# LKS_074DO_0406.net
KiCad netlist of a schematic drawn in Altium Designer
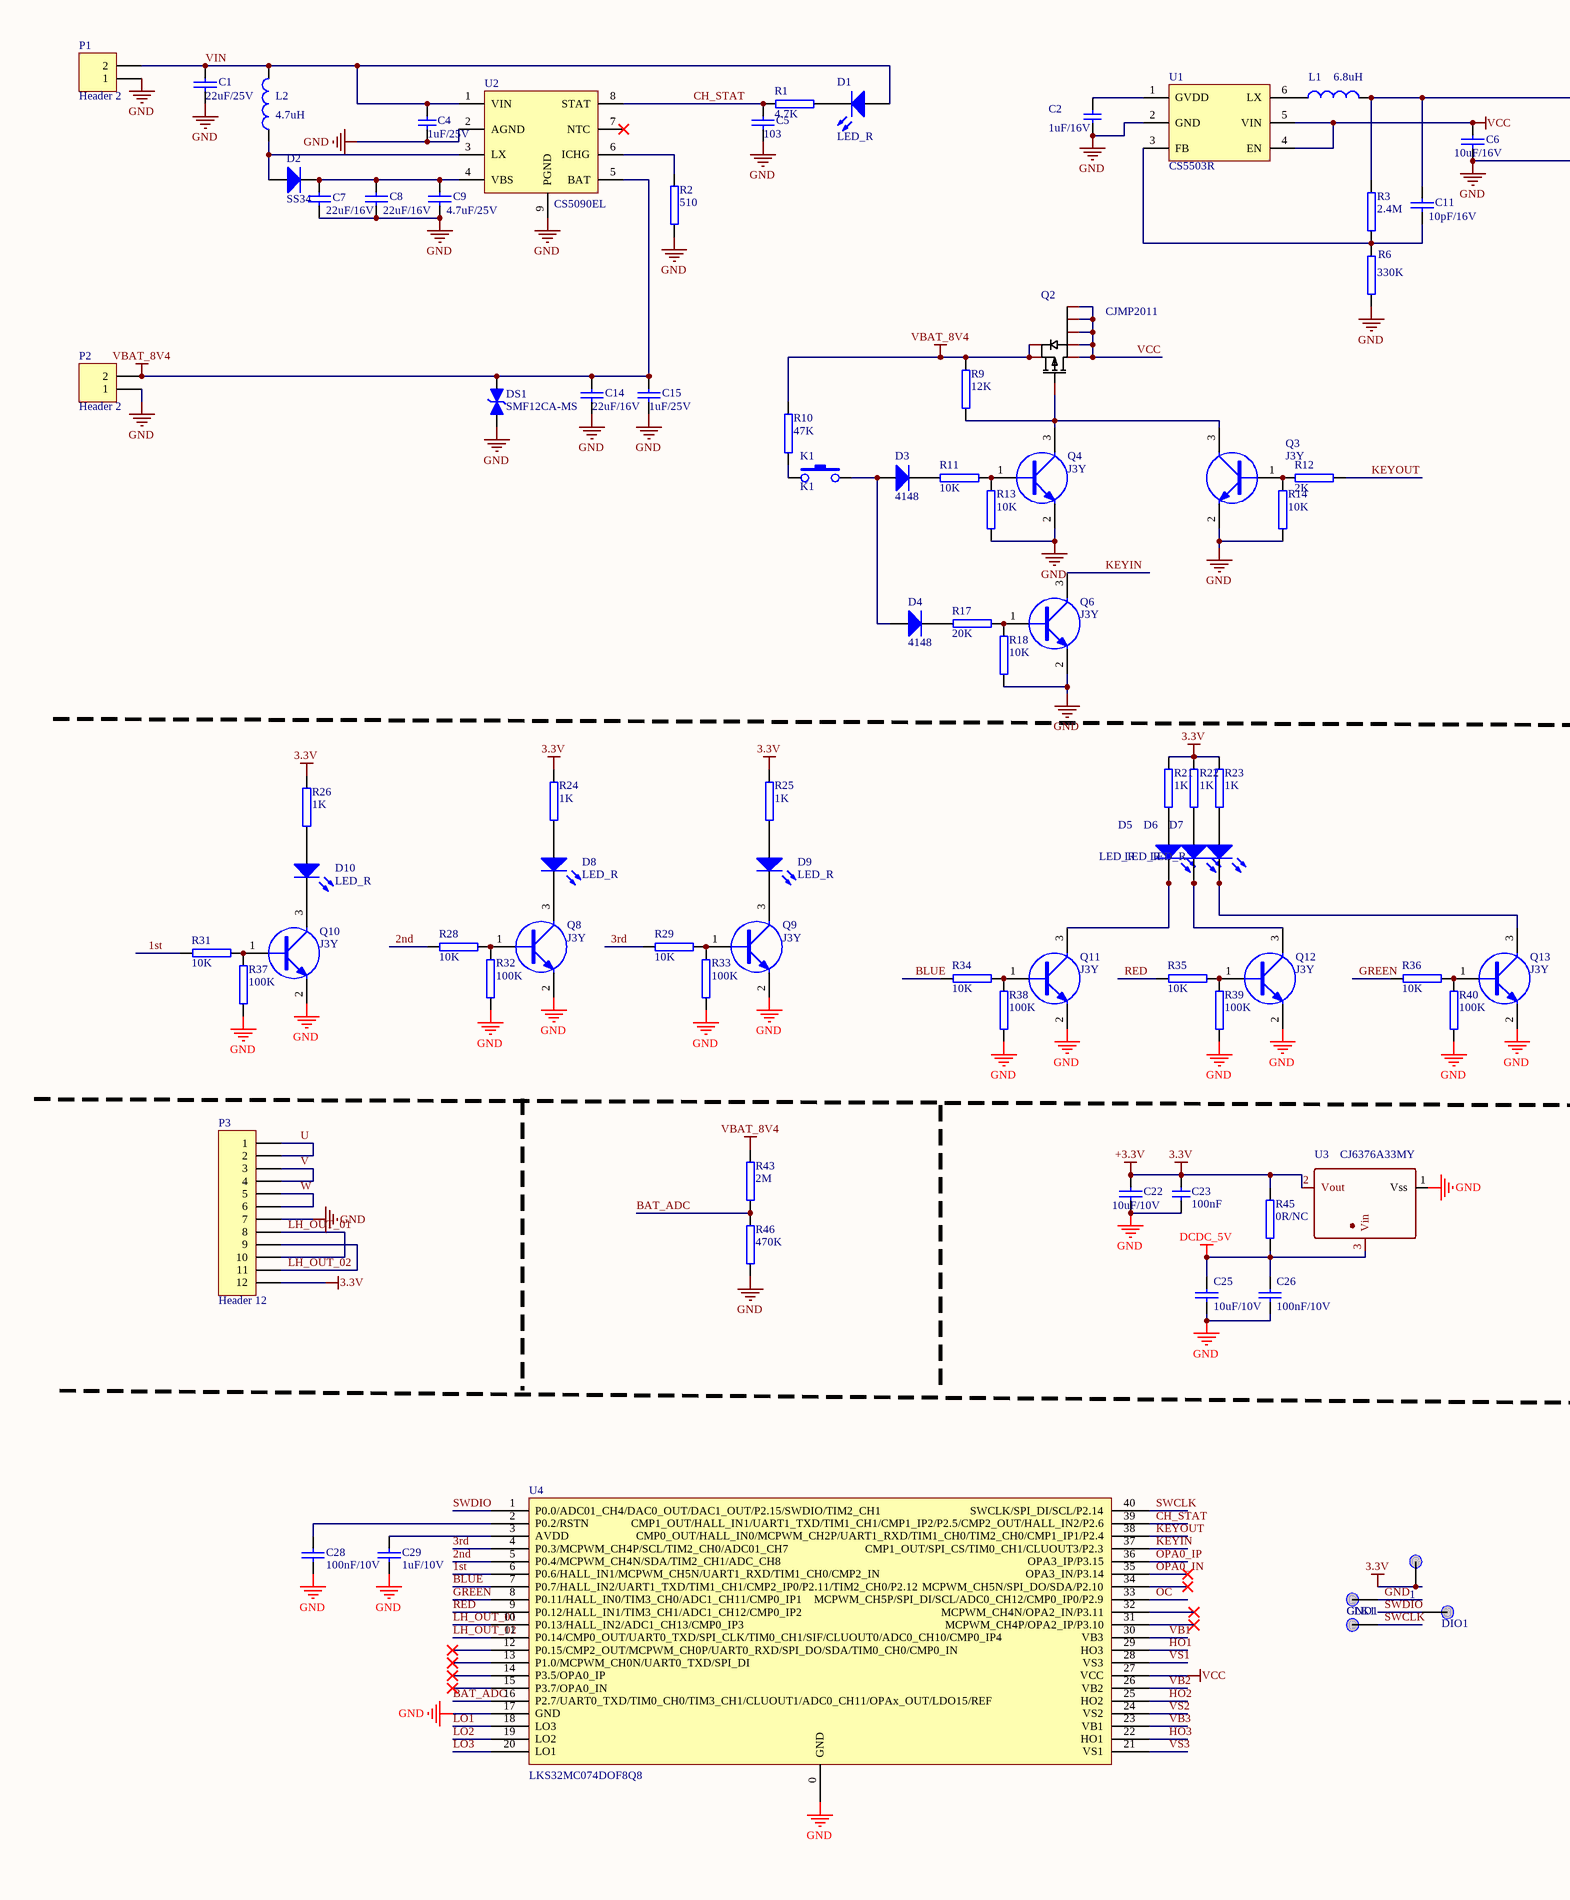
[diagram p0: LKS_074DO_0406.SchDoc, left]
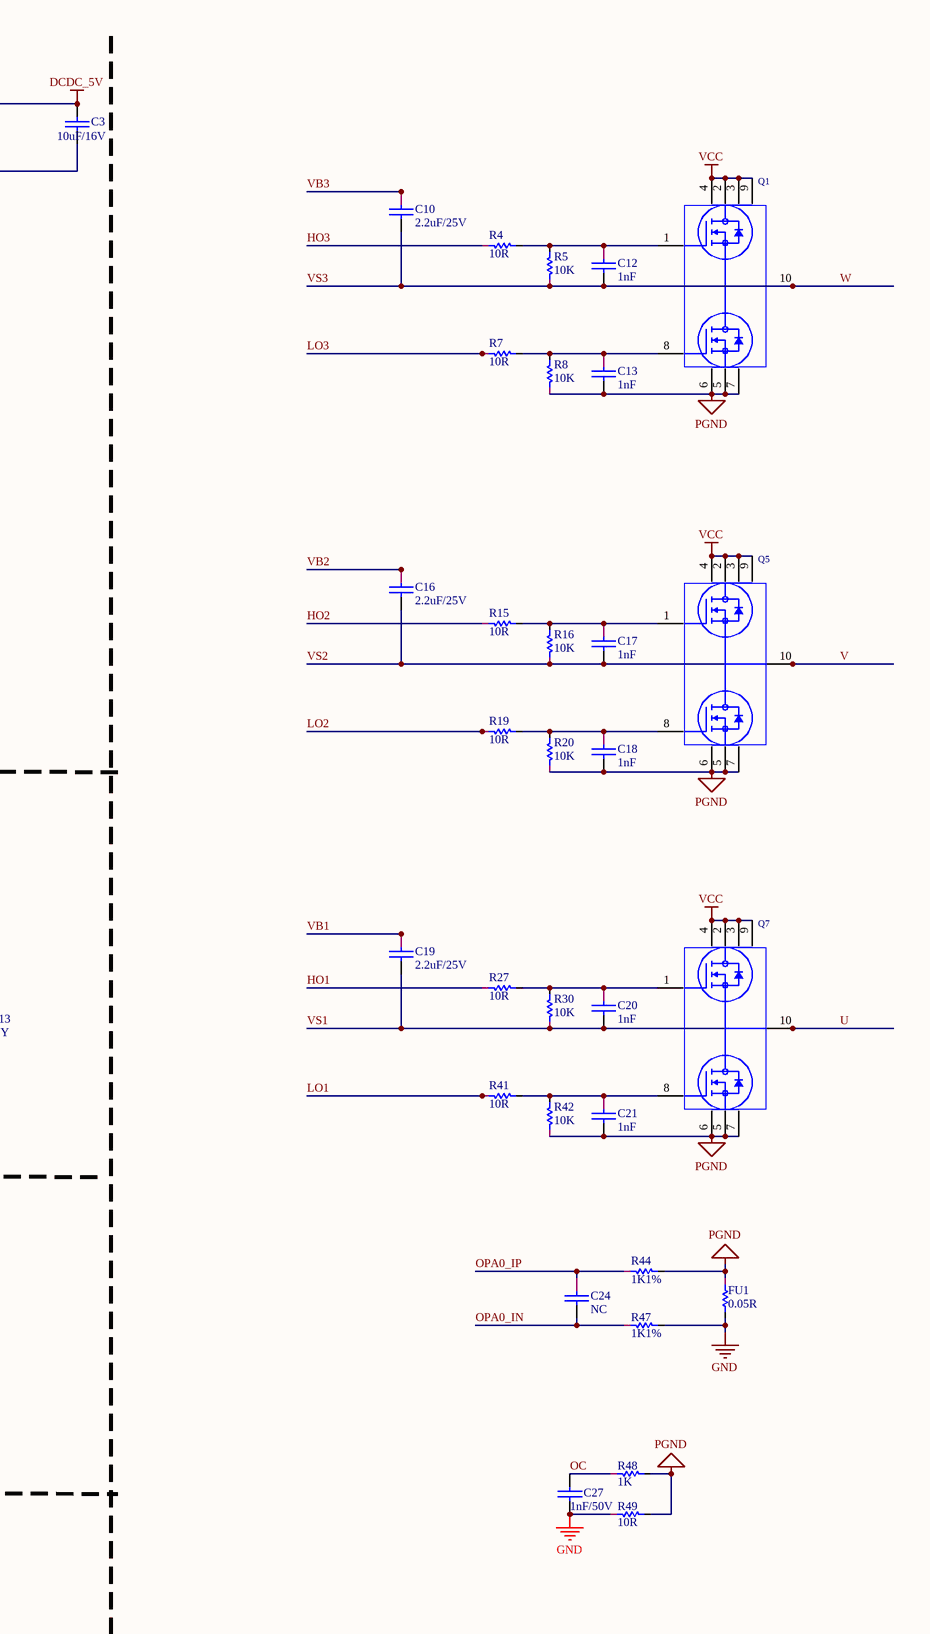
[diagram p1: LKS_074DO_0406.SchDoc, right]

(export (version "E")
  (design (tool "Eeschema 10.0.6"))
  (components
    (comp (ref "1") (value "test") (footprint "piot") (libsource (lib "LKS074DO_BRUSH_0329") (part "test")))
    (comp (ref "C1")
      (value "22uF/25V")
      (footprint "C 0603_M")
      (description "Capacitor")
      (libsource (lib "") (part "CAP_1"))
    )
    (comp (ref "C2") (value "1uF/16V") (footprint "C 0402_M") (libsource (lib "") (part "CAP_2")))
    (comp (ref "C3")
      (value "10uF/16V")
      (footprint "C 0603_M")
      (description "Capacitor")
      (libsource (lib "") (part "CAP_1"))
    )
    (comp (ref "C4") (value "1uF/25V") (footprint "C 0402_M") (libsource (lib "") (part "CAP_2")))
    (comp (ref "C5")
      (value "103")
      (footprint "R 0402_M")
      (description "Capacitor")
      (libsource (lib "") (part "CAP_1"))
    )
    (comp (ref "C6")
      (value "10uF/16V")
      (footprint "C 0603_M")
      (description "Capacitor")
      (libsource (lib "") (part "CAP_1"))
    )
    (comp (ref "C7")
      (value "22uF/16V")
      (footprint "C 0603_M")
      (description "Capacitor")
      (libsource (lib "") (part "CAP_1"))
    )
    (comp (ref "C8")
      (value "22uF/16V")
      (footprint "C 0603_M")
      (description "Capacitor")
      (libsource (lib "") (part "CAP_1"))
    )
    (comp (ref "C9")
      (value "4.7uF/25V")
      (footprint "C 0402_M")
      (description "Capacitor")
      (libsource (lib "") (part "CAP_1"))
    )
    (comp (ref "C10")
      (value "2.2uF/25V")
      (footprint "C 0402_M")
      (description "Capacitor")
      (libsource (lib "*") (part "CAP"))
    )
    (comp (ref "C11")
      (value "10pF/16V")
      (footprint "C 0402_M")
      (description "Capacitor")
      (libsource (lib "") (part "CAP_1"))
    )
    (comp (ref "C12")
      (value "1nF")
      (footprint "C 0402_M")
      (description "Capacitor")
      (libsource (lib "*") (part "CAP"))
    )
    (comp (ref "C13")
      (value "1nF")
      (footprint "C 0402_M")
      (description "Capacitor")
      (libsource (lib "*") (part "CAP"))
    )
    (comp (ref "C14")
      (value "22uF/16V")
      (footprint "C 0603_M")
      (description "Capacitor")
      (libsource (lib "") (part "CAP_1"))
    )
    (comp (ref "C15")
      (value "1uF/25V")
      (footprint "C 0402_M")
      (description "Capacitor")
      (libsource (lib "") (part "CAP_1"))
    )
    (comp (ref "C16")
      (value "2.2uF/25V")
      (footprint "C 0402_M")
      (description "Capacitor")
      (libsource (lib "*") (part "CAP"))
    )
    (comp (ref "C17")
      (value "1nF")
      (footprint "C 0402_M")
      (description "Capacitor")
      (libsource (lib "*") (part "CAP"))
    )
    (comp (ref "C18")
      (value "1nF")
      (footprint "C 0402_M")
      (description "Capacitor")
      (libsource (lib "*") (part "CAP"))
    )
    (comp (ref "C19")
      (value "2.2uF/25V")
      (footprint "C 0402_M")
      (description "Capacitor")
      (libsource (lib "*") (part "CAP"))
    )
    (comp (ref "C20")
      (value "1nF")
      (footprint "C 0402_M")
      (description "Capacitor")
      (libsource (lib "*") (part "CAP"))
    )
    (comp (ref "C21")
      (value "1nF")
      (footprint "C 0402_M")
      (description "Capacitor")
      (libsource (lib "*") (part "CAP"))
    )
    (comp (ref "C22")
      (value "10uF/10V")
      (footprint "C 0603_M")
      (description "Capacitor")
      (libsource (lib "") (part "CAP_1"))
    )
    (comp (ref "C23") (value "100nF") (footprint "C 0402_M") (libsource (lib "") (part "CAP_2")))
    (comp (ref "C24")
      (value "NC")
      (footprint "C 0402_M")
      (description "Capacitor")
      (libsource (lib "*") (part "CAP"))
    )
    (comp (ref "C25")
      (value "10uF/10V")
      (footprint "C 0603_M")
      (description "Capacitor")
      (libsource (lib "") (part "CAP_1"))
    )
    (comp (ref "C26")
      (value "100nF/10V")
      (footprint "C 0402_M")
      (description "Capacitor")
      (libsource (lib "") (part "CAP_1"))
    )
    (comp (ref "C27")
      (value "1nF/50V")
      (footprint "C 0402_M")
      (description "Capacitor")
      (libsource (lib "*") (part "C"))
    )
    (comp (ref "C28")
      (value "100nF/10V")
      (footprint "C 0402_M")
      (description "Capacitor")
      (libsource (lib "*") (part "C"))
    )
    (comp (ref "C29")
      (value "1uF/10V")
      (footprint "C 0402_M")
      (description "Capacitor")
      (libsource (lib "*") (part "C"))
    )
    (comp (ref "CLK1")
      (value "test")
      (footprint "piot")
      (libsource (lib "LKS074DO_BRUSH_0329") (part "test"))
    )
    (comp (ref "D1") (value "LED_R") (footprint "0603-LED") (libsource (lib "PuXun1") (part "LED")))
    (comp (ref "D2")
      (value "SS34")
      (footprint "SOD123FL")
      (description "Default Diode")
      (fields (field (name "PUBLISHER") "Altium Limited"))
      (libsource (lib "LKS034DO_Motor_0520_1") (part "Diode"))
    )
    (comp (ref "D3")
      (value "4148")
      (footprint "SOD-323")
      (description "Default Diode")
      (fields (field (name "PUBLISHER") "Altium Limited"))
      (libsource (lib "LKS034DO_Motor_0520_1") (part "Diode"))
    )
    (comp (ref "D4")
      (value "4148")
      (footprint "SOD-323")
      (description "Default Diode")
      (fields (field (name "PUBLISHER") "Altium Limited"))
      (libsource (lib "LKS034DO_Motor_0520_1") (part "Diode"))
    )
    (comp (ref "D5") (value "LED_R") (footprint "0603-LED") (libsource (lib "PuXun1") (part "LED")))
    (comp (ref "D6") (value "LED_R") (footprint "0603-LED") (libsource (lib "PuXun1") (part "LED")))
    (comp (ref "D7") (value "LED_R") (footprint "0603-LED") (libsource (lib "PuXun1") (part "LED")))
    (comp (ref "D8") (value "LED_R") (footprint "0603-LED") (libsource (lib "PuXun1") (part "LED")))
    (comp (ref "D9") (value "LED_R") (footprint "0603-LED") (libsource (lib "PuXun1") (part "LED")))
    (comp (ref "D10") (value "LED_R") (footprint "0603-LED") (libsource (lib "PuXun1") (part "LED")))
    (comp (ref "DIO1")
      (value "test")
      (footprint "piot")
      (libsource (lib "LKS074DO_BRUSH_0329") (part "test"))
    )
    (comp (ref "DS1")
      (value "SMF12CA-MS")
      (footprint "SOD-123F")
      (description "12V/19.9V")
      (libsource (lib "*") (part "DIODE-3"))
    )
    (comp (ref "FU1") (value "0.05R") (footprint "R 0805_M") (libsource (lib "*") (part "RAS")))
    (comp (ref "GND1")
      (value "test")
      (footprint "piot")
      (libsource (lib "LKS074DO_BRUSH_0329") (part "test"))
    )
    (comp (ref "K1") (value "K1") (footprint "SMD3.3X3.3X2") (libsource (lib "SCHLIB_NEW") (part "K1")))
    (comp (ref "L1")
      (value "6.8uH")
      (footprint "SMD3.5X3 .2- duplicate")
      (description "Inductor")
      (fields (field (name "PUBLISHER") "Altium Limited"))
      (libsource (lib "Miscellaneous Devices") (part "Inductor"))
    )
    (comp (ref "L2")
      (value "4.7uH")
      (footprint "SMD3.5X3 .2- duplicate")
      (description "Inductor")
      (fields (field (name "PUBLISHER") "Altium Limited"))
      (libsource (lib "Miscellaneous Devices") (part "Inductor"))
    )
    (comp (ref "P1")
      (value "Header 2")
      (footprint "CONN_SMD_2P_0.6")
      (description "Header, 2-Pin")
      (fields (field (name "PUBLISHER") "Altium Limited"))
      (libsource (lib "Miscellaneous Connectors") (part "Header 2"))
    )
    (comp (ref "P2")
      (value "Header 2")
      (footprint "CONN_SMD_2P_0.6")
      (description "Header, 2-Pin")
      (fields (field (name "PUBLISHER") "Altium Limited"))
      (libsource (lib "Miscellaneous Connectors") (part "Header 2"))
    )
    (comp (ref "P3")
      (value "Header 12")
      (footprint "SMD-12")
      (description "Header, 12-Pin")
      (fields (field (name "PUBLISHER") "Altium Limited"))
      (libsource (lib "Miscellaneous Connectors") (part "Header 12"))
    )
    (comp (ref "Q1") (value "CJBM3020") (footprint "DFN-3X3_8") (libsource (lib "*") (part "CJBM3020")))
    (comp (ref "Q2")
      (value "CJMP2011")
      (footprint "DFN-6-2X2")
      (libsource (lib "LKS074DO_BRUSH_0329") (part "CJMP2011"))
    )
    (comp (ref "Q3")
      (value "J3Y")
      (footprint "SOT-23")
      (description "NPN Transistor")
      (libsource (lib "*") (part "NPN"))
    )
    (comp (ref "Q4")
      (value "J3Y")
      (footprint "SOT-23")
      (description "NPN Transistor")
      (libsource (lib "*") (part "NPN"))
    )
    (comp (ref "Q5") (value "CJBM3020") (footprint "DFN-3X3_8") (libsource (lib "*") (part "CJBM3020")))
    (comp (ref "Q6")
      (value "J3Y")
      (footprint "SOT-23")
      (description "NPN Transistor")
      (libsource (lib "*") (part "NPN"))
    )
    (comp (ref "Q7") (value "CJBM3020") (footprint "DFN-3X3_8") (libsource (lib "*") (part "CJBM3020")))
    (comp (ref "Q8")
      (value "J3Y")
      (footprint "SOT-23")
      (description "NPN Transistor")
      (libsource (lib "*") (part "NPN"))
    )
    (comp (ref "Q9")
      (value "J3Y")
      (footprint "SOT-23")
      (description "NPN Transistor")
      (libsource (lib "*") (part "NPN"))
    )
    (comp (ref "Q10")
      (value "J3Y")
      (footprint "SOT-23")
      (description "NPN Transistor")
      (libsource (lib "*") (part "NPN"))
    )
    (comp (ref "Q11")
      (value "J3Y")
      (footprint "SOT-23")
      (description "NPN Transistor")
      (libsource (lib "*") (part "NPN"))
    )
    (comp (ref "Q12")
      (value "J3Y")
      (footprint "SOT-23")
      (description "NPN Transistor")
      (libsource (lib "*") (part "NPN"))
    )
    (comp (ref "Q13")
      (value "J3Y")
      (footprint "SOT-23")
      (description "NPN Transistor")
      (libsource (lib "*") (part "NPN"))
    )
    (comp (ref "R1") (value "4.7K") (footprint "C 0402_M") (libsource (lib "*") (part "RES2_S")))
    (comp (ref "R2") (value "510") (footprint "R 0402_M") (libsource (lib "*") (part "RES2_S")))
    (comp (ref "R3") (value "2.4M") (footprint "C 0402_M") (libsource (lib "*") (part "RES2_S")))
    (comp (ref "R4") (value "10R") (footprint "R 0402_M") (libsource (lib "*") (part "RAS")))
    (comp (ref "R5") (value "10K") (footprint "R 0402_M") (libsource (lib "*") (part "RAS")))
    (comp (ref "R6") (value "330K") (footprint "C 0402_M") (libsource (lib "*") (part "RES2_S")))
    (comp (ref "R7") (value "10R") (footprint "R 0402_M") (libsource (lib "*") (part "RAS")))
    (comp (ref "R8") (value "10K") (footprint "R 0402_M") (libsource (lib "*") (part "RAS")))
    (comp (ref "R9") (value "12K") (footprint "C 0402_M") (libsource (lib "*") (part "RES2_S")))
    (comp (ref "R10") (value "47K") (footprint "C 0402_M") (libsource (lib "*") (part "RES2_S")))
    (comp (ref "R11") (value "10K") (footprint "C 0402_M") (libsource (lib "*") (part "RES2_S")))
    (comp (ref "R12") (value "2K") (footprint "C 0402_M") (libsource (lib "*") (part "RES2_S")))
    (comp (ref "R13") (value "10K") (footprint "C 0402_M") (libsource (lib "*") (part "RES2_S")))
    (comp (ref "R14") (value "10K") (footprint "C 0402_M") (libsource (lib "*") (part "RES2_S")))
    (comp (ref "R15") (value "10R") (footprint "R 0402_M") (libsource (lib "*") (part "RAS")))
    (comp (ref "R16") (value "10K") (footprint "R 0402_M") (libsource (lib "*") (part "RAS")))
    (comp (ref "R17") (value "20K") (footprint "C 0402_M") (libsource (lib "*") (part "RES2_S")))
    (comp (ref "R18") (value "10K") (footprint "C 0402_M") (libsource (lib "*") (part "RES2_S")))
    (comp (ref "R19") (value "10R") (footprint "R 0402_M") (libsource (lib "*") (part "RAS")))
    (comp (ref "R20") (value "10K") (footprint "R 0402_M") (libsource (lib "*") (part "RAS")))
    (comp (ref "R21") (value "1K") (footprint "C 0402_M") (libsource (lib "*") (part "RES2_S")))
    (comp (ref "R22") (value "1K") (footprint "C 0402_M") (libsource (lib "*") (part "RES2_S")))
    (comp (ref "R23") (value "1K") (footprint "C 0402_M") (libsource (lib "*") (part "RES2_S")))
    (comp (ref "R24") (value "1K") (footprint "C 0402_M") (libsource (lib "*") (part "RES2_S")))
    (comp (ref "R25") (value "1K") (footprint "C 0402_M") (libsource (lib "*") (part "RES2_S")))
    (comp (ref "R26") (value "1K") (footprint "C 0402_M") (libsource (lib "*") (part "RES2_S")))
    (comp (ref "R27") (value "10R") (footprint "R 0402_M") (libsource (lib "*") (part "RAS")))
    (comp (ref "R28") (value "10K") (footprint "C 0402_M") (libsource (lib "*") (part "RES2_S")))
    (comp (ref "R29") (value "10K") (footprint "C 0402_M") (libsource (lib "*") (part "RES2_S")))
    (comp (ref "R30") (value "10K") (footprint "R 0402_M") (libsource (lib "*") (part "RAS")))
    (comp (ref "R31") (value "10K") (footprint "C 0402_M") (libsource (lib "*") (part "RES2_S")))
    (comp (ref "R32") (value "100K") (footprint "C 0402_M") (libsource (lib "*") (part "RES2_S")))
    (comp (ref "R33") (value "100K") (footprint "C 0402_M") (libsource (lib "*") (part "RES2_S")))
    (comp (ref "R34") (value "10K") (footprint "C 0402_M") (libsource (lib "*") (part "RES2_S")))
    (comp (ref "R35") (value "10K") (footprint "C 0402_M") (libsource (lib "*") (part "RES2_S")))
    (comp (ref "R36") (value "10K") (footprint "C 0402_M") (libsource (lib "*") (part "RES2_S")))
    (comp (ref "R37") (value "100K") (footprint "C 0402_M") (libsource (lib "*") (part "RES2_S")))
    (comp (ref "R38") (value "100K") (footprint "C 0402_M") (libsource (lib "*") (part "RES2_S")))
    (comp (ref "R39") (value "100K") (footprint "C 0402_M") (libsource (lib "*") (part "RES2_S")))
    (comp (ref "R40") (value "100K") (footprint "C 0402_M") (libsource (lib "*") (part "RES2_S")))
    (comp (ref "R41") (value "10R") (footprint "R 0402_M") (libsource (lib "*") (part "RAS")))
    (comp (ref "R42") (value "10K") (footprint "R 0402_M") (libsource (lib "*") (part "RAS")))
    (comp (ref "R43") (value "2M") (footprint "C 0402_M") (libsource (lib "*") (part "RES2_S")))
    (comp (ref "R44") (value "1K1%") (footprint "R 0402_M") (libsource (lib "*") (part "RAS")))
    (comp (ref "R45") (value "0R/NC") (footprint "0603") (libsource (lib "*") (part "RES2_S")))
    (comp (ref "R46") (value "470K") (footprint "C 0402_M") (libsource (lib "*") (part "RES2_S")))
    (comp (ref "R47") (value "1K1%") (footprint "R 0402_M") (libsource (lib "*") (part "RAS")))
    (comp (ref "R48") (value "1K") (footprint "R 0402_M") (libsource (lib "*") (part "RAS")))
    (comp (ref "R49") (value "10R") (footprint "R 0402_M") (libsource (lib "*") (part "RAS")))
    (comp (ref "U1")
      (value "CS5503R")
      (footprint "SOT23-6L")
      (libsource (lib "LKS034DO_Motor_0520_1") (part "CS5503R"))
    )
    (comp (ref "U2")
      (value "CS5090EL")
      (footprint "DFN2X2_8_0.5")
      (libsource (lib "LKS034DO_Motor_0520_1") (part "CS5090EL"))
    )
    (comp (ref "U3")
      (value "CJ6376A33MY")
      (footprint "SOT-23")
      (libsource (lib "LKS074DO_BRUSH_0329") (part "78L15"))
    )
    (comp (ref "U4")
      (value "LKS32MC074DOF8Q8")
      (footprint "QFN40")
      (description "芯片")
      (libsource (lib "Q_LINKO_V1.0") (part "LKS32MC074DF8Q8"))
    )
  )
  (nets
    (net (code "1") (name "+3.3V") (class "Default")
      (node (ref "1") (pin "1") (pinfunction "1_1") (pintype "passive"))
      (node (ref "C22") (pin "2") (pinfunction "2_2") (pintype "passive"))
      (node (ref "C23") (pin "1") (pinfunction "1_1") (pintype "passive"))
      (node (ref "P3") (pin "12") (pinfunction "12_12") (pintype "passive"))
      (node (ref "R21") (pin "2") (pinfunction "2_2") (pintype "passive"))
      (node (ref "R22") (pin "2") (pinfunction "2_2") (pintype "passive"))
      (node (ref "R23") (pin "2") (pinfunction "2_2") (pintype "passive"))
      (node (ref "R24") (pin "2") (pinfunction "2_2") (pintype "passive"))
      (node (ref "R25") (pin "2") (pinfunction "2_2") (pintype "passive"))
      (node (ref "R26") (pin "2") (pinfunction "2_2") (pintype "passive"))
      (node (ref "R45") (pin "2") (pinfunction "2_2") (pintype "passive"))
      (node (ref "U3") (pin "2") (pinfunction "Vout_2") (pintype "passive"))
    )
    (net (code "2") (name "/1st") (class "Default")
      (node (ref "R31") (pin "2") (pinfunction "2_2") (pintype "passive"))
      (node (ref "U4") (pin "6") (pinfunction "P0.6/HALL_IN1/MCPWM_CH5N/UART1_RXD/TIM1_CH0/CMP2_IN_6") (pintype "passive"))
    )
    (net (code "3") (name "/2nd") (class "Default")
      (node (ref "R28") (pin "2") (pinfunction "2_2") (pintype "passive"))
      (node (ref "U4") (pin "5") (pinfunction "P0.4/MCPWM_CH4N/SDA/TIM2_CH1/ADC_CH8_5") (pintype "passive"))
    )
    (net (code "4") (name "/3rd") (class "Default")
      (node (ref "R29") (pin "2") (pinfunction "2_2") (pintype "passive"))
      (node (ref "U4") (pin "4") (pinfunction "P0.3/MCPWM_CH4P/SCL/TIM2_CH0/ADC01_CH7_4") (pintype "passive"))
    )
    (net (code "5") (name "/BAT_ADC") (class "Default")
      (node (ref "R43") (pin "2") (pinfunction "2_2") (pintype "passive"))
      (node (ref "R46") (pin "1") (pinfunction "1_1") (pintype "passive"))
      (node (ref "U4") (pin "16") (pinfunction "P2.7/UART0_TXD/TIM0_CH0/TIM3_CH1/CLUOUT1/ADC0_CH11/OPAx_OUT/LDO15/REF_16") (pintype "passive"))
    )
    (net (code "6") (name "/BLUE") (class "Default")
      (node (ref "R34") (pin "2") (pinfunction "2_2") (pintype "passive"))
      (node (ref "U4") (pin "7") (pinfunction "P0.7/HALL_IN2/UART1_TXD/TIM1_CH1/CMP2_IP0/P2.11/TIM2_CH0/P2.12_7") (pintype "passive"))
    )
    (net (code "7") (name "/CH_STAT") (class "Default")
      (node (ref "C5") (pin "2") (pinfunction "2_2") (pintype "passive"))
      (node (ref "R1") (pin "1") (pinfunction "1_1") (pintype "passive"))
      (node (ref "U2") (pin "8") (pinfunction "STAT_8") (pintype "passive"))
      (node (ref "U4") (pin "39") (pinfunction "CMP1_OUT/HALL_IN1/UART1_TXD/TIM1_CH1/CMP1_IP2/P2.5/CMP2_OUT/HALL_IN2/P2.6_39") (pintype "passive"))
    )
    (net (code "8") (name "/GREEN") (class "Default")
      (node (ref "R36") (pin "2") (pinfunction "2_2") (pintype "passive"))
      (node (ref "U4") (pin "8") (pinfunction "P0.11/HALL_IN0/TIM3_CH0/ADC1_CH11/CMP0_IP1_8") (pintype "passive"))
    )
    (net (code "9") (name "/HO1") (class "Default")
      (node (ref "R27") (pin "2") (pinfunction "2_2") (pintype "passive"))
      (node (ref "U4") (pin "29") (pinfunction "HO3_29") (pintype "passive"))
    )
    (net (code "10") (name "/HO2") (class "Default")
      (node (ref "R15") (pin "2") (pinfunction "2_2") (pintype "passive"))
      (node (ref "U4") (pin "25") (pinfunction "HO2_25") (pintype "passive"))
    )
    (net (code "11") (name "/HO3") (class "Default")
      (node (ref "R4") (pin "2") (pinfunction "2_2") (pintype "passive"))
      (node (ref "U4") (pin "22") (pinfunction "HO1_22") (pintype "passive"))
    )
    (net (code "12") (name "/KEYIN") (class "Default")
      (node (ref "Q6") (pin "3") (pinfunction "C_3") (pintype "passive"))
      (node (ref "U4") (pin "37") (pinfunction "CMP1_OUT/SPI_CS/TIM0_CH1/CLUOUT3/P2.3_37") (pintype "passive"))
    )
    (net (code "13") (name "/KEYOUT") (class "Default")
      (node (ref "R12") (pin "2") (pinfunction "2_2") (pintype "passive"))
      (node (ref "U4") (pin "38") (pinfunction "CMP0_OUT/HALL_IN0/MCPWM_CH2P/UART1_RXD/TIM1_CH0/TIM2_CH0/CMP1_IP1/P2.4_38") (pintype "passive"))
    )
    (net (code "14") (name "/LH_OUT_01") (class "Default")
      (node (ref "P3") (pin "10") (pinfunction "10_10") (pintype "passive"))
      (node (ref "P3") (pin "8") (pinfunction "8_8") (pintype "passive"))
      (node (ref "U4") (pin "10") (pinfunction "P0.13/HALL_IN2/ADC1_CH13/CMP0_IP3_10") (pintype "passive"))
    )
    (net (code "15") (name "/LH_OUT_02") (class "Default")
      (node (ref "P3") (pin "11") (pinfunction "11_11") (pintype "passive"))
      (node (ref "P3") (pin "9") (pinfunction "9_9") (pintype "passive"))
      (node (ref "U4") (pin "11") (pinfunction "P0.14/CMP0_OUT/UART0_TXD/SPI_CLK/TIM0_CH1/SIF/CLUOUT0/ADC0_CH10/CMP0_IP4_11") (pintype "passive"))
    )
    (net (code "16") (name "/LO1") (class "Default")
      (node (ref "R41") (pin "2") (pinfunction "2_2") (pintype "passive"))
      (node (ref "U4") (pin "18") (pinfunction "LO3_18") (pintype "passive"))
    )
    (net (code "17") (name "/LO2") (class "Default")
      (node (ref "R19") (pin "2") (pinfunction "2_2") (pintype "passive"))
      (node (ref "U4") (pin "19") (pinfunction "LO2_19") (pintype "passive"))
    )
    (net (code "18") (name "/LO3") (class "Default")
      (node (ref "R7") (pin "2") (pinfunction "2_2") (pintype "passive"))
      (node (ref "U4") (pin "20") (pinfunction "LO1_20") (pintype "passive"))
    )
    (net (code "19") (name "/OC") (class "Default")
      (node (ref "C27") (pin "2") (pinfunction "2_2") (pintype "passive"))
      (node (ref "R48") (pin "2") (pinfunction "2_2") (pintype "passive"))
      (node (ref "U4") (pin "33") (pinfunction "MCPWM_CH5P/SPI_DI/SCL/ADC0_CH12/CMP0_IP0/P2.9_33") (pintype "passive"))
    )
    (net (code "20") (name "/OPA0_IN") (class "Default")
      (node (ref "C24") (pin "1") (pinfunction "1_1") (pintype "passive"))
      (node (ref "R47") (pin "2") (pinfunction "2_2") (pintype "passive"))
      (node (ref "U4") (pin "35") (pinfunction "OPA3_IN/P3.14_35") (pintype "passive"))
    )
    (net (code "21") (name "/OPA0_IP") (class "Default")
      (node (ref "C24") (pin "2") (pinfunction "2_2") (pintype "passive"))
      (node (ref "R44") (pin "2") (pinfunction "2_2") (pintype "passive"))
      (node (ref "U4") (pin "36") (pinfunction "OPA3_IP/P3.15_36") (pintype "passive"))
    )
    (net (code "22") (name "/RED") (class "Default")
      (node (ref "R35") (pin "2") (pinfunction "2_2") (pintype "passive"))
      (node (ref "U4") (pin "9") (pinfunction "P0.12/HALL_IN1/TIM3_CH1/ADC1_CH12/CMP0_IP2_9") (pintype "passive"))
    )
    (net (code "23") (name "/SWCLK") (class "Default")
      (node (ref "CLK1") (pin "1") (pinfunction "1_1") (pintype "passive"))
      (node (ref "U4") (pin "40") (pinfunction "SWCLK/SPI_DI/SCL/P2.14_40") (pintype "passive"))
    )
    (net (code "24") (name "/SWDIO") (class "Default")
      (node (ref "DIO1") (pin "1") (pinfunction "1_1") (pintype "passive"))
      (node (ref "U4") (pin "1") (pinfunction "P0.0/ADC01_CH4/DAC0_OUT/DAC1_OUT/P2.15/SWDIO/TIM2_CH1_1") (pintype "passive"))
    )
    (net (code "25") (name "/U") (class "Default")
      (node (ref "C19") (pin "1") (pinfunction "1_1") (pintype "passive"))
      (node (ref "C20") (pin "1") (pinfunction "1_1") (pintype "passive"))
      (node (ref "P3") (pin "1") (pinfunction "1_1") (pintype "passive"))
      (node (ref "P3") (pin "2") (pinfunction "2_2") (pintype "passive"))
      (node (ref "Q7") (pin "10") (pinfunction "S1/D2_10") (pintype "passive"))
      (node (ref "R30") (pin "2") (pinfunction "2_2") (pintype "passive"))
      (node (ref "U4") (pin "28") (pinfunction "VS3_28") (pintype "passive"))
    )
    (net (code "26") (name "/V") (class "Default")
      (node (ref "C16") (pin "1") (pinfunction "1_1") (pintype "passive"))
      (node (ref "C17") (pin "1") (pinfunction "1_1") (pintype "passive"))
      (node (ref "P3") (pin "3") (pinfunction "3_3") (pintype "passive"))
      (node (ref "P3") (pin "4") (pinfunction "4_4") (pintype "passive"))
      (node (ref "Q5") (pin "10") (pinfunction "S1/D2_10") (pintype "passive"))
      (node (ref "R16") (pin "2") (pinfunction "2_2") (pintype "passive"))
      (node (ref "U4") (pin "24") (pinfunction "VS2_24") (pintype "passive"))
    )
    (net (code "27") (name "/VB1") (class "Default")
      (node (ref "C19") (pin "2") (pinfunction "2_2") (pintype "passive"))
      (node (ref "U4") (pin "30") (pinfunction "VB3_30") (pintype "passive"))
    )
    (net (code "28") (name "/VB2") (class "Default")
      (node (ref "C16") (pin "2") (pinfunction "2_2") (pintype "passive"))
      (node (ref "U4") (pin "26") (pinfunction "VB2_26") (pintype "passive"))
    )
    (net (code "29") (name "/VB3") (class "Default")
      (node (ref "C10") (pin "2") (pinfunction "2_2") (pintype "passive"))
      (node (ref "U4") (pin "23") (pinfunction "VB1_23") (pintype "passive"))
    )
    (net (code "30") (name "/VIN") (class "Default")
      (node (ref "C1") (pin "2") (pinfunction "2_2") (pintype "passive"))
      (node (ref "C4") (pin "1") (pinfunction "1_1") (pintype "passive"))
      (node (ref "D1") (pin "1") (pinfunction "A_1") (pintype "passive"))
      (node (ref "L2") (pin "2") (pinfunction "2_2") (pintype "passive"))
      (node (ref "P1") (pin "2") (pinfunction "2_2") (pintype "passive"))
      (node (ref "U2") (pin "1") (pinfunction "VIN_1") (pintype "passive"))
    )
    (net (code "31") (name "/VS3") (class "Default")
      (node (ref "C10") (pin "1") (pinfunction "1_1") (pintype "passive"))
      (node (ref "C12") (pin "1") (pinfunction "1_1") (pintype "passive"))
      (node (ref "P3") (pin "5") (pinfunction "5_5") (pintype "passive"))
      (node (ref "P3") (pin "6") (pinfunction "6_6") (pintype "passive"))
      (node (ref "Q1") (pin "10") (pinfunction "S1/D2_10") (pintype "passive"))
      (node (ref "R5") (pin "2") (pinfunction "2_2") (pintype "passive"))
      (node (ref "U4") (pin "21") (pinfunction "VS1_21") (pintype "passive"))
    )
    (net (code "32") (name "DCDC_5V") (class "Default")
      (node (ref "C11") (pin "2") (pinfunction "2_2") (pintype "passive"))
      (node (ref "C25") (pin "2") (pinfunction "2_2") (pintype "passive"))
      (node (ref "C26") (pin "1") (pinfunction "1_1") (pintype "passive"))
      (node (ref "C3") (pin "2") (pinfunction "2_2") (pintype "passive"))
      (node (ref "L1") (pin "2") (pinfunction "2_2") (pintype "passive"))
      (node (ref "R3") (pin "1") (pinfunction "1_1") (pintype "passive"))
      (node (ref "R45") (pin "1") (pinfunction "1_1") (pintype "passive"))
      (node (ref "U3") (pin "3") (pinfunction "Vin_3") (pintype "passive"))
    )
    (net (code "33") (name "GND") (class "Default")
      (node (ref "C1") (pin "1") (pinfunction "1_1") (pintype "passive"))
      (node (ref "C14") (pin "1") (pinfunction "1_1") (pintype "passive"))
      (node (ref "C15") (pin "1") (pinfunction "1_1") (pintype "passive"))
      (node (ref "C2") (pin "1") (pinfunction "1_1") (pintype "passive"))
      (node (ref "C22") (pin "1") (pinfunction "1_1") (pintype "passive"))
      (node (ref "C23") (pin "2") (pinfunction "2_2") (pintype "passive"))
      (node (ref "C25") (pin "1") (pinfunction "1_1") (pintype "passive"))
      (node (ref "C26") (pin "2") (pinfunction "2_2") (pintype "passive"))
      (node (ref "C27") (pin "1") (pinfunction "1_1") (pintype "passive"))
      (node (ref "C28") (pin "2") (pinfunction "2_2") (pintype "passive"))
      (node (ref "C29") (pin "1") (pinfunction "1_1") (pintype "passive"))
      (node (ref "C3") (pin "1") (pinfunction "1_1") (pintype "passive"))
      (node (ref "C4") (pin "2") (pinfunction "2_2") (pintype "passive"))
      (node (ref "C5") (pin "1") (pinfunction "1_1") (pintype "passive"))
      (node (ref "C6") (pin "1") (pinfunction "1_1") (pintype "passive"))
      (node (ref "C7") (pin "1") (pinfunction "1_1") (pintype "passive"))
      (node (ref "C8") (pin "1") (pinfunction "1_1") (pintype "passive"))
      (node (ref "C9") (pin "1") (pinfunction "1_1") (pintype "passive"))
      (node (ref "DS1") (pin "2") (pinfunction "K_2") (pintype "passive"))
      (node (ref "FU1") (pin "1") (pinfunction "1_1") (pintype "passive"))
      (node (ref "GND1") (pin "1") (pinfunction "1_1") (pintype "passive"))
      (node (ref "P1") (pin "1") (pinfunction "1_1") (pintype "passive"))
      (node (ref "P2") (pin "1") (pinfunction "1_1") (pintype "passive"))
      (node (ref "P3") (pin "7") (pinfunction "7_7") (pintype "passive"))
      (node (ref "Q10") (pin "2") (pinfunction "E_2") (pintype "passive"))
      (node (ref "Q11") (pin "2") (pinfunction "E_2") (pintype "passive"))
      (node (ref "Q12") (pin "2") (pinfunction "E_2") (pintype "passive"))
      (node (ref "Q13") (pin "2") (pinfunction "E_2") (pintype "passive"))
      (node (ref "Q3") (pin "2") (pinfunction "E_2") (pintype "passive"))
      (node (ref "Q4") (pin "2") (pinfunction "E_2") (pintype "passive"))
      (node (ref "Q6") (pin "2") (pinfunction "E_2") (pintype "passive"))
      (node (ref "Q8") (pin "2") (pinfunction "E_2") (pintype "passive"))
      (node (ref "Q9") (pin "2") (pinfunction "E_2") (pintype "passive"))
      (node (ref "R13") (pin "1") (pinfunction "1_1") (pintype "passive"))
      (node (ref "R14") (pin "1") (pinfunction "1_1") (pintype "passive"))
      (node (ref "R18") (pin "1") (pinfunction "1_1") (pintype "passive"))
      (node (ref "R2") (pin "2") (pinfunction "2_2") (pintype "passive"))
      (node (ref "R32") (pin "2") (pinfunction "2_2") (pintype "passive"))
      (node (ref "R33") (pin "2") (pinfunction "2_2") (pintype "passive"))
      (node (ref "R37") (pin "2") (pinfunction "2_2") (pintype "passive"))
      (node (ref "R38") (pin "2") (pinfunction "2_2") (pintype "passive"))
      (node (ref "R39") (pin "2") (pinfunction "2_2") (pintype "passive"))
      (node (ref "R40") (pin "2") (pinfunction "2_2") (pintype "passive"))
      (node (ref "R46") (pin "2") (pinfunction "2_2") (pintype "passive"))
      (node (ref "R47") (pin "1") (pinfunction "1_1") (pintype "passive"))
      (node (ref "R49") (pin "2") (pinfunction "2_2") (pintype "passive"))
      (node (ref "R6") (pin "2") (pinfunction "2_2") (pintype "passive"))
      (node (ref "U1") (pin "2") (pinfunction "GND_2") (pintype "passive"))
      (node (ref "U2") (pin "2") (pinfunction "AGND_2") (pintype "passive"))
      (node (ref "U2") (pin "9") (pinfunction "PGND_9") (pintype "passive"))
      (node (ref "U3") (pin "1") (pinfunction "Vss_1") (pintype "passive"))
      (node (ref "U4") (pin "0") (pinfunction "GND_0") (pintype "passive"))
      (node (ref "U4") (pin "17") (pinfunction "GND_17") (pintype "passive"))
    )
    (net (code "34") (name "Net-(D1-K)") (class "Default")
      (node (ref "D1") (pin "2") (pinfunction "K_2") (pintype "passive"))
      (node (ref "R1") (pin "2") (pinfunction "2_2") (pintype "passive"))
    )
    (net (code "35") (name "Net-(D2-A)") (class "Default")
      (node (ref "D2") (pin "1") (pinfunction "A_1") (pintype "passive"))
      (node (ref "L2") (pin "1") (pinfunction "1_1") (pintype "passive"))
      (node (ref "U2") (pin "3") (pinfunction "LX_3") (pintype "passive"))
    )
    (net (code "36") (name "Net-(D2-K)") (class "Default")
      (node (ref "C7") (pin "2") (pinfunction "2_2") (pintype "passive"))
      (node (ref "C8") (pin "2") (pinfunction "2_2") (pintype "passive"))
      (node (ref "C9") (pin "2") (pinfunction "2_2") (pintype "passive"))
      (node (ref "D2") (pin "2") (pinfunction "K_2") (pintype "passive"))
      (node (ref "U2") (pin "4") (pinfunction "VBS_4") (pintype "passive"))
    )
    (net (code "37") (name "Net-(D3-A)") (class "Default")
      (node (ref "D3") (pin "1") (pinfunction "A_1") (pintype "passive"))
      (node (ref "D4") (pin "1") (pinfunction "A_1") (pintype "passive"))
      (node (ref "K1") (pin "2") (pintype "passive"))
    )
    (net (code "38") (name "Net-(D3-K)") (class "Default")
      (node (ref "D3") (pin "2") (pinfunction "K_2") (pintype "passive"))
      (node (ref "R11") (pin "1") (pinfunction "1_1") (pintype "passive"))
    )
    (net (code "39") (name "Net-(D4-K)") (class "Default")
      (node (ref "D4") (pin "2") (pinfunction "K_2") (pintype "passive"))
      (node (ref "R17") (pin "1") (pinfunction "1_1") (pintype "passive"))
    )
    (net (code "40") (name "Net-(D5-A)") (class "Default")
      (node (ref "D5") (pin "1") (pinfunction "A_1") (pintype "passive"))
      (node (ref "R21") (pin "1") (pinfunction "1_1") (pintype "passive"))
    )
    (net (code "41") (name "Net-(D5-K)") (class "Default")
      (node (ref "D5") (pin "2") (pinfunction "K_2") (pintype "passive"))
      (node (ref "Q11") (pin "3") (pinfunction "C_3") (pintype "passive"))
    )
    (net (code "42") (name "Net-(D6-A)") (class "Default")
      (node (ref "D6") (pin "1") (pinfunction "A_1") (pintype "passive"))
      (node (ref "R22") (pin "1") (pinfunction "1_1") (pintype "passive"))
    )
    (net (code "43") (name "Net-(D6-K)") (class "Default")
      (node (ref "D6") (pin "2") (pinfunction "K_2") (pintype "passive"))
      (node (ref "Q12") (pin "3") (pinfunction "C_3") (pintype "passive"))
    )
    (net (code "44") (name "Net-(D7-A)") (class "Default")
      (node (ref "D7") (pin "1") (pinfunction "A_1") (pintype "passive"))
      (node (ref "R23") (pin "1") (pinfunction "1_1") (pintype "passive"))
    )
    (net (code "45") (name "Net-(D7-K)") (class "Default")
      (node (ref "D7") (pin "2") (pinfunction "K_2") (pintype "passive"))
      (node (ref "Q13") (pin "3") (pinfunction "C_3") (pintype "passive"))
    )
    (net (code "46") (name "Net-(D8-A)") (class "Default")
      (node (ref "D8") (pin "1") (pinfunction "A_1") (pintype "passive"))
      (node (ref "R24") (pin "1") (pinfunction "1_1") (pintype "passive"))
    )
    (net (code "47") (name "Net-(D8-K)") (class "Default")
      (node (ref "D8") (pin "2") (pinfunction "K_2") (pintype "passive"))
      (node (ref "Q8") (pin "3") (pinfunction "C_3") (pintype "passive"))
    )
    (net (code "48") (name "Net-(D9-A)") (class "Default")
      (node (ref "D9") (pin "1") (pinfunction "A_1") (pintype "passive"))
      (node (ref "R25") (pin "1") (pinfunction "1_1") (pintype "passive"))
    )
    (net (code "49") (name "Net-(D9-K)") (class "Default")
      (node (ref "D9") (pin "2") (pinfunction "K_2") (pintype "passive"))
      (node (ref "Q9") (pin "3") (pinfunction "C_3") (pintype "passive"))
    )
    (net (code "50") (name "Net-(D10-A)") (class "Default")
      (node (ref "D10") (pin "1") (pinfunction "A_1") (pintype "passive"))
      (node (ref "R26") (pin "1") (pinfunction "1_1") (pintype "passive"))
    )
    (net (code "51") (name "Net-(D10-K)") (class "Default")
      (node (ref "D10") (pin "2") (pinfunction "K_2") (pintype "passive"))
      (node (ref "Q10") (pin "3") (pinfunction "C_3") (pintype "passive"))
    )
    (net (code "52") (name "Net-(K1-Pad1)") (class "Default")
      (node (ref "K1") (pin "1") (pintype "passive"))
      (node (ref "R10") (pin "1") (pinfunction "1_1") (pintype "passive"))
    )
    (net (code "53") (name "Net-(Q1-G1)") (class "Default")
      (node (ref "C12") (pin "2") (pinfunction "2_2") (pintype "passive"))
      (node (ref "Q1") (pin "1") (pinfunction "G1_1") (pintype "passive"))
      (node (ref "R4") (pin "1") (pinfunction "1_1") (pintype "passive"))
      (node (ref "R5") (pin "1") (pinfunction "1_1") (pintype "passive"))
    )
    (net (code "54") (name "Net-(Q1-G2)") (class "Default")
      (node (ref "C13") (pin "2") (pinfunction "2_2") (pintype "passive"))
      (node (ref "Q1") (pin "8") (pinfunction "G2_8") (pintype "passive"))
      (node (ref "R7") (pin "1") (pinfunction "1_1") (pintype "passive"))
      (node (ref "R8") (pin "1") (pinfunction "1_1") (pintype "passive"))
    )
    (net (code "55") (name "Net-(Q2-G)") (class "Default")
      (node (ref "Q2") (pin "3") (pinfunction "G_3") (pintype "passive"))
      (node (ref "Q3") (pin "3") (pinfunction "C_3") (pintype "passive"))
      (node (ref "Q4") (pin "3") (pinfunction "C_3") (pintype "passive"))
      (node (ref "R9") (pin "1") (pinfunction "1_1") (pintype "passive"))
    )
    (net (code "56") (name "Net-(Q3-B)") (class "Default")
      (node (ref "Q3") (pin "1") (pinfunction "B_1") (pintype "passive"))
      (node (ref "R12") (pin "1") (pinfunction "1_1") (pintype "passive"))
      (node (ref "R14") (pin "2") (pinfunction "2_2") (pintype "passive"))
    )
    (net (code "57") (name "Net-(Q4-B)") (class "Default")
      (node (ref "Q4") (pin "1") (pinfunction "B_1") (pintype "passive"))
      (node (ref "R11") (pin "2") (pinfunction "2_2") (pintype "passive"))
      (node (ref "R13") (pin "2") (pinfunction "2_2") (pintype "passive"))
    )
    (net (code "58") (name "Net-(Q5-G1)") (class "Default")
      (node (ref "C17") (pin "2") (pinfunction "2_2") (pintype "passive"))
      (node (ref "Q5") (pin "1") (pinfunction "G1_1") (pintype "passive"))
      (node (ref "R15") (pin "1") (pinfunction "1_1") (pintype "passive"))
      (node (ref "R16") (pin "1") (pinfunction "1_1") (pintype "passive"))
    )
    (net (code "59") (name "Net-(Q5-G2)") (class "Default")
      (node (ref "C18") (pin "2") (pinfunction "2_2") (pintype "passive"))
      (node (ref "Q5") (pin "8") (pinfunction "G2_8") (pintype "passive"))
      (node (ref "R19") (pin "1") (pinfunction "1_1") (pintype "passive"))
      (node (ref "R20") (pin "1") (pinfunction "1_1") (pintype "passive"))
    )
    (net (code "60") (name "Net-(Q6-B)") (class "Default")
      (node (ref "Q6") (pin "1") (pinfunction "B_1") (pintype "passive"))
      (node (ref "R17") (pin "2") (pinfunction "2_2") (pintype "passive"))
      (node (ref "R18") (pin "2") (pinfunction "2_2") (pintype "passive"))
    )
    (net (code "61") (name "Net-(Q7-G1)") (class "Default")
      (node (ref "C20") (pin "2") (pinfunction "2_2") (pintype "passive"))
      (node (ref "Q7") (pin "1") (pinfunction "G1_1") (pintype "passive"))
      (node (ref "R27") (pin "1") (pinfunction "1_1") (pintype "passive"))
      (node (ref "R30") (pin "1") (pinfunction "1_1") (pintype "passive"))
    )
    (net (code "62") (name "Net-(Q7-G2)") (class "Default")
      (node (ref "C21") (pin "2") (pinfunction "2_2") (pintype "passive"))
      (node (ref "Q7") (pin "8") (pinfunction "G2_8") (pintype "passive"))
      (node (ref "R41") (pin "1") (pinfunction "1_1") (pintype "passive"))
      (node (ref "R42") (pin "1") (pinfunction "1_1") (pintype "passive"))
    )
    (net (code "63") (name "Net-(Q8-B)") (class "Default")
      (node (ref "Q8") (pin "1") (pinfunction "B_1") (pintype "passive"))
      (node (ref "R28") (pin "1") (pinfunction "1_1") (pintype "passive"))
      (node (ref "R32") (pin "1") (pinfunction "1_1") (pintype "passive"))
    )
    (net (code "64") (name "Net-(Q9-B)") (class "Default")
      (node (ref "Q9") (pin "1") (pinfunction "B_1") (pintype "passive"))
      (node (ref "R29") (pin "1") (pinfunction "1_1") (pintype "passive"))
      (node (ref "R33") (pin "1") (pinfunction "1_1") (pintype "passive"))
    )
    (net (code "65") (name "Net-(Q10-B)") (class "Default")
      (node (ref "Q10") (pin "1") (pinfunction "B_1") (pintype "passive"))
      (node (ref "R31") (pin "1") (pinfunction "1_1") (pintype "passive"))
      (node (ref "R37") (pin "1") (pinfunction "1_1") (pintype "passive"))
    )
    (net (code "66") (name "Net-(Q11-B)") (class "Default")
      (node (ref "Q11") (pin "1") (pinfunction "B_1") (pintype "passive"))
      (node (ref "R34") (pin "1") (pinfunction "1_1") (pintype "passive"))
      (node (ref "R38") (pin "1") (pinfunction "1_1") (pintype "passive"))
    )
    (net (code "67") (name "Net-(Q12-B)") (class "Default")
      (node (ref "Q12") (pin "1") (pinfunction "B_1") (pintype "passive"))
      (node (ref "R35") (pin "1") (pinfunction "1_1") (pintype "passive"))
      (node (ref "R39") (pin "1") (pinfunction "1_1") (pintype "passive"))
    )
    (net (code "68") (name "Net-(Q13-B)") (class "Default")
      (node (ref "Q13") (pin "1") (pinfunction "B_1") (pintype "passive"))
      (node (ref "R36") (pin "1") (pinfunction "1_1") (pintype "passive"))
      (node (ref "R40") (pin "1") (pinfunction "1_1") (pintype "passive"))
    )
    (net (code "69") (name "Net-(U1-FB)") (class "Default")
      (node (ref "C11") (pin "1") (pinfunction "1_1") (pintype "passive"))
      (node (ref "R3") (pin "2") (pinfunction "2_2") (pintype "passive"))
      (node (ref "R6") (pin "1") (pinfunction "1_1") (pintype "passive"))
      (node (ref "U1") (pin "3") (pinfunction "FB_3") (pintype "passive"))
    )
    (net (code "70") (name "Net-(U1-GVDD)") (class "Default")
      (node (ref "C2") (pin "2") (pinfunction "2_2") (pintype "passive"))
      (node (ref "U1") (pin "1") (pinfunction "GVDD_1") (pintype "passive"))
    )
    (net (code "71") (name "Net-(U1-LX)") (class "Default")
      (node (ref "L1") (pin "1") (pinfunction "1_1") (pintype "passive"))
      (node (ref "U1") (pin "6") (pinfunction "LX_6") (pintype "passive"))
    )
    (net (code "72") (name "Net-(U2-ICHG)") (class "Default")
      (node (ref "R2") (pin "1") (pinfunction "1_1") (pintype "passive"))
      (node (ref "U2") (pin "6") (pinfunction "ICHG_6") (pintype "passive"))
    )
    (net (code "73") (name "Net-(U4-AVDD)") (class "Default")
      (node (ref "C29") (pin "2") (pinfunction "2_2") (pintype "passive"))
      (node (ref "U4") (pin "3") (pinfunction "AVDD_3") (pintype "passive"))
    )
    (net (code "74") (name "Net-(U4-P0.2{slash}RSTN)") (class "Default")
      (node (ref "C28") (pin "1") (pinfunction "1_1") (pintype "passive"))
      (node (ref "U4") (pin "2") (pinfunction "P0.2/RSTN_2") (pintype "passive"))
    )
    (net (code "75") (name "PGND") (class "Default")
      (node (ref "C13") (pin "1") (pinfunction "1_1") (pintype "passive"))
      (node (ref "C18") (pin "1") (pinfunction "1_1") (pintype "passive"))
      (node (ref "C21") (pin "1") (pinfunction "1_1") (pintype "passive"))
      (node (ref "FU1") (pin "2") (pinfunction "2_2") (pintype "passive"))
      (node (ref "Q1") (pin "5") (pinfunction "S2_5") (pintype "passive"))
      (node (ref "Q1") (pin "6") (pinfunction "S2_6") (pintype "passive"))
      (node (ref "Q1") (pin "7") (pinfunction "S2_7") (pintype "passive"))
      (node (ref "Q5") (pin "5") (pinfunction "S2_5") (pintype "passive"))
      (node (ref "Q5") (pin "6") (pinfunction "S2_6") (pintype "passive"))
      (node (ref "Q5") (pin "7") (pinfunction "S2_7") (pintype "passive"))
      (node (ref "Q7") (pin "5") (pinfunction "S2_5") (pintype "passive"))
      (node (ref "Q7") (pin "6") (pinfunction "S2_6") (pintype "passive"))
      (node (ref "Q7") (pin "7") (pinfunction "S2_7") (pintype "passive"))
      (node (ref "R20") (pin "2") (pinfunction "2_2") (pintype "passive"))
      (node (ref "R42") (pin "2") (pinfunction "2_2") (pintype "passive"))
      (node (ref "R44") (pin "1") (pinfunction "1_1") (pintype "passive"))
      (node (ref "R48") (pin "1") (pinfunction "1_1") (pintype "passive"))
      (node (ref "R49") (pin "1") (pinfunction "1_1") (pintype "passive"))
      (node (ref "R8") (pin "2") (pinfunction "2_2") (pintype "passive"))
    )
    (net (code "76") (name "VBAT_8V4") (class "Default")
      (node (ref "C14") (pin "2") (pinfunction "2_2") (pintype "passive"))
      (node (ref "C15") (pin "2") (pinfunction "2_2") (pintype "passive"))
      (node (ref "DS1") (pin "1") (pinfunction "A_1") (pintype "passive"))
      (node (ref "P2") (pin "2") (pinfunction "2_2") (pintype "passive"))
      (node (ref "Q2") (pin "4") (pinfunction "S_4") (pintype "passive"))
      (node (ref "Q2") (pin "8") (pinfunction "S_8") (pintype "passive"))
      (node (ref "R10") (pin "2") (pinfunction "2_2") (pintype "passive"))
      (node (ref "R43") (pin "1") (pinfunction "1_1") (pintype "passive"))
      (node (ref "R9") (pin "2") (pinfunction "2_2") (pintype "passive"))
      (node (ref "U2") (pin "5") (pinfunction "BAT_5") (pintype "passive"))
    )
    (net (code "77") (name "VCC") (class "Default")
      (node (ref "C6") (pin "2") (pinfunction "2_2") (pintype "passive"))
      (node (ref "Q1") (pin "2") (pinfunction "D1_2") (pintype "passive"))
      (node (ref "Q1") (pin "3") (pinfunction "D1_3") (pintype "passive"))
      (node (ref "Q1") (pin "4") (pinfunction "D1_4") (pintype "passive"))
      (node (ref "Q1") (pin "9") (pinfunction "D1_9") (pintype "passive"))
      (node (ref "Q2") (pin "1") (pinfunction "D_1") (pintype "passive"))
      (node (ref "Q2") (pin "2") (pinfunction "D_2") (pintype "passive"))
      (node (ref "Q2") (pin "5") (pinfunction "D_5") (pintype "passive"))
      (node (ref "Q2") (pin "6") (pinfunction "D_6") (pintype "passive"))
      (node (ref "Q2") (pin "7") (pinfunction "D_7") (pintype "passive"))
      (node (ref "Q5") (pin "2") (pinfunction "D1_2") (pintype "passive"))
      (node (ref "Q5") (pin "3") (pinfunction "D1_3") (pintype "passive"))
      (node (ref "Q5") (pin "4") (pinfunction "D1_4") (pintype "passive"))
      (node (ref "Q5") (pin "9") (pinfunction "D1_9") (pintype "passive"))
      (node (ref "Q7") (pin "2") (pinfunction "D1_2") (pintype "passive"))
      (node (ref "Q7") (pin "3") (pinfunction "D1_3") (pintype "passive"))
      (node (ref "Q7") (pin "4") (pinfunction "D1_4") (pintype "passive"))
      (node (ref "Q7") (pin "9") (pinfunction "D1_9") (pintype "passive"))
      (node (ref "U1") (pin "4") (pinfunction "EN_4") (pintype "passive"))
      (node (ref "U1") (pin "5") (pinfunction "VIN_5") (pintype "passive"))
      (node (ref "U4") (pin "27") (pinfunction "VCC_27") (pintype "passive"))
    )
    (net (code "78") (name "unconnected-(U2-NTC-Pad7)") (class "Default")
      (node (ref "U2") (pin "7") (pinfunction "NTC_7") (pintype "passive+no_connect"))
    )
    (net (code "79") (name "unconnected-(U4-MCPWM_CH4N{slash}OPA2_IN{slash}P3.11-Pad32)") (class "Default")
      (node (ref "U4") (pin "32") (pinfunction "MCPWM_CH4N/OPA2_IN/P3.11_32") (pintype "passive+no_connect"))
    )
    (net (code "80") (name "unconnected-(U4-MCPWM_CH4P{slash}OPA2_IP{slash}P3.10-Pad31)") (class "Default")
      (node (ref "U4") (pin "31") (pinfunction "MCPWM_CH4P/OPA2_IP/P3.10_31") (pintype "passive+no_connect"))
    )
    (net (code "81") (name "unconnected-(U4-MCPWM_CH5N{slash}SPI_DO{slash}SDA{slash}P2.10-Pad34)") (class "Default")
      (node (ref "U4") (pin "34") (pinfunction "MCPWM_CH5N/SPI_DO/SDA/P2.10_34") (pintype "passive+no_connect"))
    )
    (net (code "82") (name "unconnected-(U4-P0.15{slash}CMP2_OUT{slash}MCPWM_CH0P{slash}UART0_RXD{slash}SPI_DO{slash}SDA{slash}TIM0_CH0{slash}CMP0_IN-Pad12)") (class "Default")
      (node (ref "U4") (pin "12") (pinfunction "P0.15/CMP2_OUT/MCPWM_CH0P/UART0_RXD/SPI_DO/SDA/TIM0_CH0/CMP0_IN_12") (pintype "passive+no_connect"))
    )
    (net (code "83") (name "unconnected-(U4-P1.0{slash}MCPWM_CH0N{slash}UART0_TXD{slash}SPI_DI-Pad13)") (class "Default")
      (node (ref "U4") (pin "13") (pinfunction "P1.0/MCPWM_CH0N/UART0_TXD/SPI_DI_13") (pintype "passive+no_connect"))
    )
    (net (code "84") (name "unconnected-(U4-P3.5{slash}OPA0_IP-Pad14)") (class "Default")
      (node (ref "U4") (pin "14") (pinfunction "P3.5/OPA0_IP_14") (pintype "passive+no_connect"))
    )
    (net (code "85") (name "unconnected-(U4-P3.7{slash}OPA0_IN-Pad15)") (class "Default")
      (node (ref "U4") (pin "15") (pinfunction "P3.7/OPA0_IN_15") (pintype "passive+no_connect"))
    )
  )
)
